# ESC.net
KiCad netlist of a schematic drawn in Altium Designer
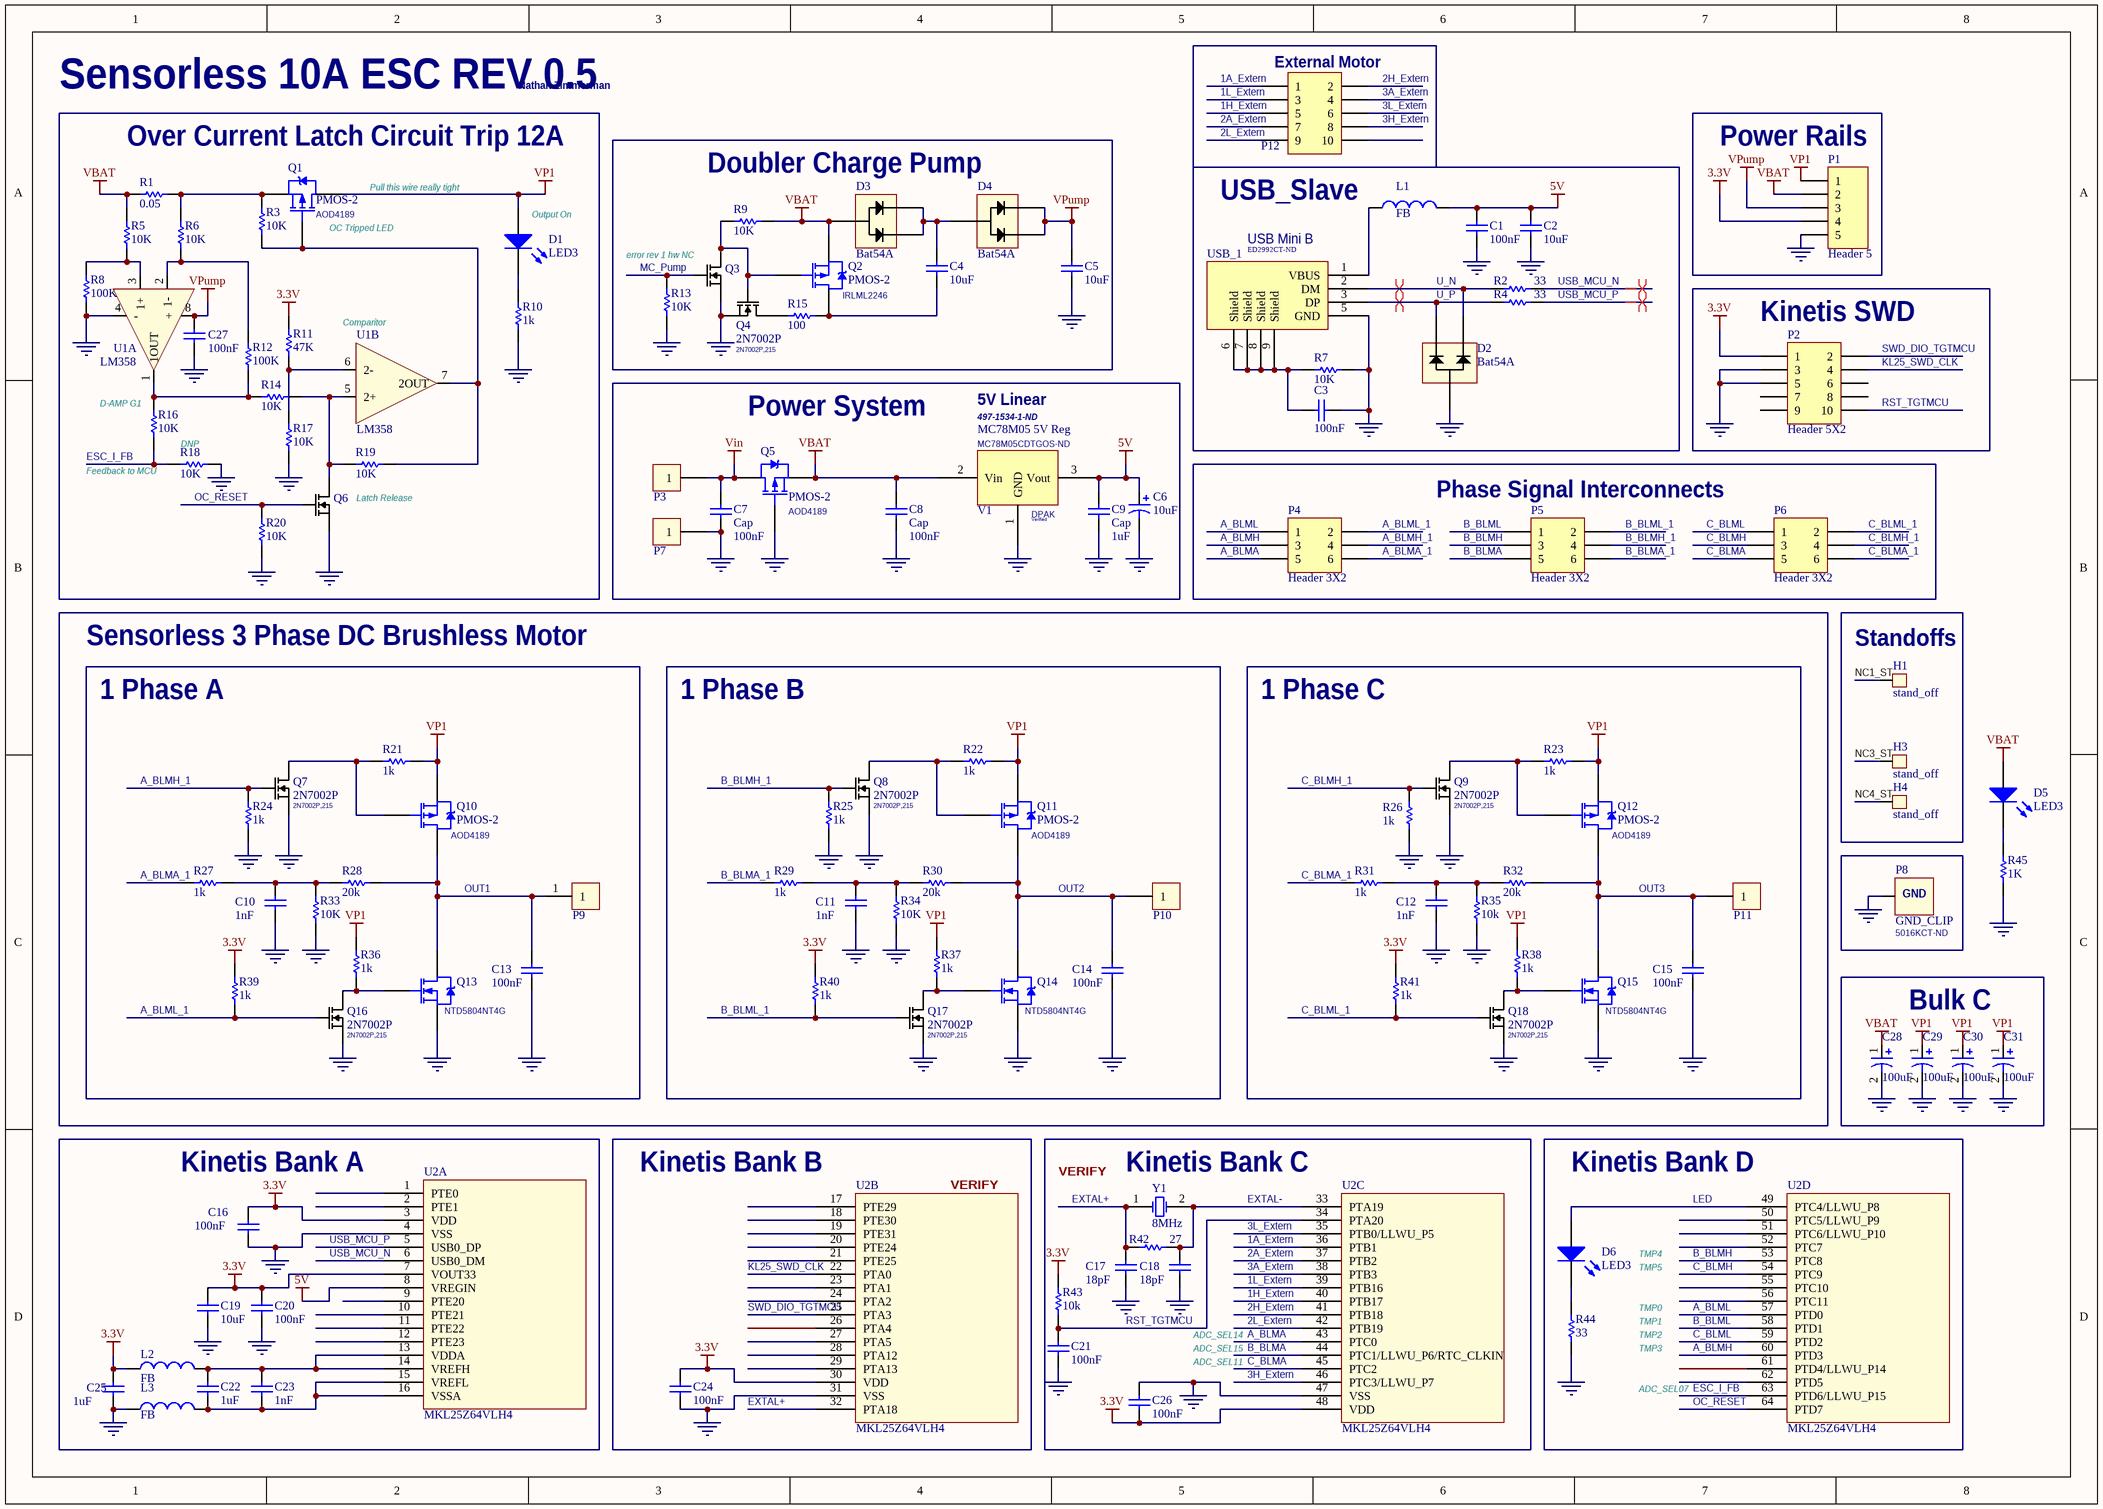
[diagram p0: ESC.SchDoc]

(export (version "E")
  (design (tool "Eeschema 10.0.6"))
  (components
    (comp (ref "C1")
      (value "100nF")
      (footprint "1608[0603]")
      (description "Capacitor (Semiconductor SIM Model)")
      (fields (field (name "Comment") "0805") (field (name "PUBLISHER") "Altium Limited"))
      (libsource (lib "Miscellaneous Devices") (part "Cap Semi"))
    )
    (comp (ref "C2")
      (value "10uF")
      (footprint "C0805")
      (description "Capacitor (Semiconductor SIM Model)")
      (fields (field (name "Comment") "0805") (field (name "PUBLISHER") "Altium Limited"))
      (libsource (lib "Miscellaneous Devices") (part "Cap Semi"))
    )
    (comp (ref "C3")
      (value "100nF")
      (footprint "1608[0603]")
      (description "Capacitor (Semiconductor SIM Model)")
      (fields (field (name "Comment") "0805") (field (name "PUBLISHER") "Altium Limited"))
      (libsource (lib "Miscellaneous Devices") (part "Cap Semi"))
    )
    (comp (ref "C4")
      (value "10uF")
      (footprint "C0805")
      (description "Capacitor (Semiconductor SIM Model)")
      (fields (field (name "Comment") "0805") (field (name "PUBLISHER") "Altium Limited"))
      (libsource (lib "Miscellaneous Devices") (part "Cap Semi"))
    )
    (comp (ref "C5")
      (value "10uF")
      (footprint "C0805")
      (description "Capacitor (Semiconductor SIM Model)")
      (fields (field (name "Comment") "0805") (field (name "PUBLISHER") "Altium Limited"))
      (libsource (lib "Miscellaneous Devices") (part "Cap Semi"))
    )
    (comp (ref "C6")
      (value "10uF")
      (footprint "1206_C")
      (description "Polarized Capacitor (Radial)")
      (fields (field (name "Comment") "Cap Pol1"))
      (libsource (lib "Miscellaneous Devices") (part "Cap Pol1"))
    )
    (comp (ref "C7")
      (value "Cap")
      (footprint "C0805")
      (description "Capacitor")
      (fields (field (name "ALTIUM_VALUE") "100nF") (field (name "PUBLISHER") "Altium Limited"))
      (libsource (lib "Miscellaneous Devices") (part "Cap"))
    )
    (comp (ref "C8")
      (value "Cap")
      (footprint "C0805")
      (description "Capacitor")
      (fields (field (name "ALTIUM_VALUE") "100nF") (field (name "PUBLISHER") "Altium Limited"))
      (libsource (lib "Miscellaneous Devices") (part "Cap"))
    )
    (comp (ref "C9")
      (value "Cap")
      (footprint "C0805")
      (description "Capacitor")
      (fields (field (name "ALTIUM_VALUE") "1uF") (field (name "PUBLISHER") "Altium Limited"))
      (libsource (lib "Miscellaneous Devices") (part "Cap"))
    )
    (comp (ref "C10")
      (value "1nF")
      (footprint "1608[0603]")
      (description "Capacitor (Semiconductor SIM Model)")
      (fields (field (name "Comment") "0805") (field (name "PUBLISHER") "Altium Limited"))
      (libsource (lib "Miscellaneous Devices") (part "Cap Semi"))
    )
    (comp (ref "C11")
      (value "1nF")
      (footprint "1608[0603]")
      (description "Capacitor (Semiconductor SIM Model)")
      (fields (field (name "Comment") "0805") (field (name "PUBLISHER") "Altium Limited"))
      (libsource (lib "Miscellaneous Devices") (part "Cap Semi"))
    )
    (comp (ref "C12")
      (value "1nF")
      (footprint "1608[0603]")
      (description "Capacitor (Semiconductor SIM Model)")
      (fields (field (name "Comment") "0805") (field (name "PUBLISHER") "Altium Limited"))
      (libsource (lib "Miscellaneous Devices") (part "Cap Semi"))
    )
    (comp (ref "C13")
      (value "100nF")
      (footprint "1608[0603]")
      (description "Capacitor (Semiconductor SIM Model)")
      (fields (field (name "Comment") "0805") (field (name "PUBLISHER") "Altium Limited"))
      (libsource (lib "Miscellaneous Devices") (part "Cap Semi"))
    )
    (comp (ref "C14")
      (value "100nF")
      (footprint "1608[0603]")
      (description "Capacitor (Semiconductor SIM Model)")
      (fields (field (name "Comment") "0805") (field (name "PUBLISHER") "Altium Limited"))
      (libsource (lib "Miscellaneous Devices") (part "Cap Semi"))
    )
    (comp (ref "C15")
      (value "100nF")
      (footprint "1608[0603]")
      (description "Capacitor (Semiconductor SIM Model)")
      (fields (field (name "Comment") "0805") (field (name "PUBLISHER") "Altium Limited"))
      (libsource (lib "Miscellaneous Devices") (part "Cap Semi"))
    )
    (comp (ref "C16")
      (value "100nF")
      (footprint "1608[0603]")
      (description "Capacitor (Semiconductor SIM Model)")
      (fields (field (name "Comment") "0805") (field (name "PUBLISHER") "Altium Limited"))
      (libsource (lib "Miscellaneous Devices") (part "Cap Semi"))
    )
    (comp (ref "C17")
      (value "18pF")
      (footprint "1608[0603]")
      (description "Capacitor (Semiconductor SIM Model)")
      (fields (field (name "Comment") "0805") (field (name "PUBLISHER") "Altium Limited"))
      (libsource (lib "Miscellaneous Devices") (part "Cap Semi"))
    )
    (comp (ref "C18")
      (value "18pF")
      (footprint "1608[0603]")
      (description "Capacitor (Semiconductor SIM Model)")
      (fields (field (name "Comment") "0805") (field (name "PUBLISHER") "Altium Limited"))
      (libsource (lib "Miscellaneous Devices") (part "Cap Semi"))
    )
    (comp (ref "C19")
      (value "10uF")
      (footprint "C0805")
      (description "Capacitor (Semiconductor SIM Model)")
      (fields (field (name "Comment") "0805") (field (name "PUBLISHER") "Altium Limited"))
      (libsource (lib "Miscellaneous Devices") (part "Cap Semi"))
    )
    (comp (ref "C20")
      (value "100nF")
      (footprint "1608[0603]")
      (description "Capacitor (Semiconductor SIM Model)")
      (fields (field (name "Comment") "0805") (field (name "PUBLISHER") "Altium Limited"))
      (libsource (lib "Miscellaneous Devices") (part "Cap Semi"))
    )
    (comp (ref "C21")
      (value "100nF")
      (footprint "1608[0603]")
      (description "Capacitor (Semiconductor SIM Model)")
      (fields (field (name "Comment") "0805") (field (name "PUBLISHER") "Altium Limited"))
      (libsource (lib "Miscellaneous Devices") (part "Cap Semi"))
    )
    (comp (ref "C22")
      (value "1uF")
      (footprint "1608[0603]")
      (description "Capacitor (Semiconductor SIM Model)")
      (fields (field (name "Comment") "0805") (field (name "PUBLISHER") "Altium Limited"))
      (libsource (lib "Miscellaneous Devices") (part "Cap Semi"))
    )
    (comp (ref "C23")
      (value "1nF")
      (footprint "1608[0603]")
      (description "Capacitor (Semiconductor SIM Model)")
      (fields (field (name "Comment") "0805") (field (name "PUBLISHER") "Altium Limited"))
      (libsource (lib "Miscellaneous Devices") (part "Cap Semi"))
    )
    (comp (ref "C24")
      (value "100nF")
      (footprint "1608[0603]")
      (description "Capacitor (Semiconductor SIM Model)")
      (fields (field (name "Comment") "0805") (field (name "PUBLISHER") "Altium Limited"))
      (libsource (lib "Miscellaneous Devices") (part "Cap Semi"))
    )
    (comp (ref "C25")
      (value "1uF")
      (footprint "1608[0603]")
      (description "Capacitor (Semiconductor SIM Model)")
      (fields (field (name "Comment") "0805") (field (name "PUBLISHER") "Altium Limited"))
      (libsource (lib "Miscellaneous Devices") (part "Cap Semi"))
    )
    (comp (ref "C26")
      (value "100nF")
      (footprint "1608[0603]")
      (description "Capacitor (Semiconductor SIM Model)")
      (fields (field (name "Comment") "0805") (field (name "PUBLISHER") "Altium Limited"))
      (libsource (lib "Miscellaneous Devices") (part "Cap Semi"))
    )
    (comp (ref "C27")
      (value "100nF")
      (footprint "1608[0603]")
      (description "Capacitor (Semiconductor SIM Model)")
      (fields (field (name "Comment") "0805"))
      (libsource (lib "Miscellaneous Devices") (part "Cap Semi"))
    )
    (comp (ref "C28")
      (value "100uF")
      (footprint "ELE_CAP")
      (description "Polarized Capacitor (Radial)")
      (fields (field (name "Comment") "Cap Pol1"))
      (libsource (lib "") (part "Cap Pol1_1"))
    )
    (comp (ref "C29")
      (value "100uF")
      (footprint "ELE_CAP")
      (description "Polarized Capacitor (Radial)")
      (fields (field (name "Comment") "Cap Pol1"))
      (libsource (lib "") (part "Cap Pol1_1"))
    )
    (comp (ref "C30")
      (value "100uF")
      (footprint "ELE_CAP")
      (description "Polarized Capacitor (Radial)")
      (fields (field (name "Comment") "Cap Pol1"))
      (libsource (lib "") (part "Cap Pol1_1"))
    )
    (comp (ref "C31")
      (value "100uF")
      (footprint "ELE_CAP")
      (description "Polarized Capacitor (Radial)")
      (fields (field (name "Comment") "Cap Pol1"))
      (libsource (lib "") (part "Cap Pol1_1"))
    )
    (comp (ref "D1")
      (value "LED3")
      (footprint "6-0805_L")
      (description "Typical BLUE SiC LED")
      (fields (field (name "PUBLISHER") "Altium Limited"))
      (libsource (lib "Miscellaneous Devices") (part "LED3"))
    )
    (comp (ref "D2")
      (value "Bat54A")
      (footprint "SOT-23B_N")
      (description "Bat45C")
      (libsource (lib "GSOT05CGS08") (part "Bat45C"))
    )
    (comp (ref "D3")
      (value "Bat54A")
      (footprint "SOT-23B_N")
      (description "Bat45C")
      (libsource (lib "GSOT05CGS08") (part "Bat45C"))
    )
    (comp (ref "D4")
      (value "Bat54A")
      (footprint "SOT-23B_N")
      (description "Bat45C")
      (libsource (lib "GSOT05CGS08") (part "Bat45C"))
    )
    (comp (ref "D5")
      (value "LED3")
      (footprint "6-0805_L")
      (description "Typical BLUE SiC LED")
      (fields (field (name "PUBLISHER") "Altium Limited"))
      (libsource (lib "Miscellaneous Devices") (part "LED3"))
    )
    (comp (ref "D6")
      (value "LED3")
      (footprint "6-0805_L")
      (description "Typical BLUE SiC LED")
      (fields (field (name "PUBLISHER") "Altium Limited"))
      (libsource (lib "Miscellaneous Devices") (part "LED3"))
    )
    (comp (ref "H1")
      (value "stand_off")
      (footprint "4-40_screw_hole")
      (libsource (lib "pcb_standoff") (part "stand_off"))
    )
    (comp (ref "H3")
      (value "stand_off")
      (footprint "4-40_screw_hole")
      (libsource (lib "pcb_standoff") (part "stand_off"))
    )
    (comp (ref "H4")
      (value "stand_off")
      (footprint "4-40_screw_hole")
      (libsource (lib "pcb_standoff") (part "stand_off"))
    )
    (comp (ref "L1")
      (value "FB")
      (footprint "1608[0603]")
      (description "Inductor")
      (libsource (lib "Miscellaneous Devices") (part "Inductor"))
    )
    (comp (ref "L2")
      (value "FB")
      (footprint "1608[0603]")
      (description "Inductor")
      (libsource (lib "Miscellaneous Devices") (part "Inductor"))
    )
    (comp (ref "L3")
      (value "FB")
      (footprint "1608[0603]")
      (description "Inductor")
      (libsource (lib "Miscellaneous Devices") (part "Inductor"))
    )
    (comp (ref "P1")
      (value "Header 5")
      (footprint "HDR1X5")
      (description "Header, 5-Pin")
      (fields (field (name "PUBLISHER") "Altium Limited"))
      (libsource (lib "Miscellaneous Connectors") (part "Header 5"))
    )
    (comp (ref "P2")
      (value "Header 5X2")
      (footprint "MHDR2X5")
      (description "Header, 5-Pin, Dual row")
      (fields (field (name "PUBLISHER") "Altium Limited"))
      (libsource (lib "Miscellaneous Connectors") (part "Header 5X2"))
    )
    (comp (ref "P3") (value "Header") (footprint "8191_K") (libsource (lib "Header1") (part "Header1h1")))
    (comp (ref "P4")
      (value "Header 3X2")
      (footprint "HDR2X3")
      (description "Header, 3-Pin, Dual row")
      (fields (field (name "PUBLISHER") "Altium Limited"))
      (libsource (lib "Miscellaneous Connectors") (part "Header 3X2"))
    )
    (comp (ref "P5")
      (value "Header 3X2")
      (footprint "HDR2X3")
      (description "Header, 3-Pin, Dual row")
      (fields (field (name "PUBLISHER") "Altium Limited"))
      (libsource (lib "Miscellaneous Connectors") (part "Header 3X2"))
    )
    (comp (ref "P6")
      (value "Header 3X2")
      (footprint "HDR2X3")
      (description "Header, 3-Pin, Dual row")
      (fields (field (name "PUBLISHER") "Altium Limited"))
      (libsource (lib "Miscellaneous Connectors") (part "Header 3X2"))
    )
    (comp (ref "P7") (value "Header") (footprint "8191_K") (libsource (lib "Header1") (part "Header1h1")))
    (comp (ref "P8")
      (value "GND_CLIP")
      (footprint "GND_CLIP")
      (fields (field (name "ALTIUM_UNNAMED_1") "5016KCT-ND"))
      (libsource (lib "GND_CLIP") (part "GND_CLIP"))
    )
    (comp (ref "P9") (value "Header") (footprint "8191_K") (libsource (lib "") (part "Header1h1_1")))
    (comp (ref "P10") (value "Header") (footprint "8191_K") (libsource (lib "Header1") (part "Header1h1")))
    (comp (ref "P11") (value "Header") (footprint "8191_K") (libsource (lib "Header1") (part "Header1h1")))
    (comp (ref "P12")
      (value "Header 5X2")
      (footprint "HDR2X5")
      (description "Header, 5-Pin, Dual row")
      (fields (field (name "PUBLISHER") "Altium Limited"))
      (libsource (lib "Miscellaneous Connectors") (part "Header 5X2"))
    )
    (comp (ref "Q1")
      (value "PMOS-2")
      (footprint "TO228P970-3_4AM")
      (description "P-Channel Power MOSFET")
      (fields (field (name "ALTIUM_UNNAMED_1") "AOD4189"))
      (libsource (lib "Miscellaneous Devices") (part "PMOS-2"))
    )
    (comp (ref "Q2")
      (value "PMOS-2")
      (footprint "SOT-23_M")
      (description "P-Channel Power MOSFET")
      (fields (field (name "ALTIUM_UNNAMED_1") "IRLML2246"))
      (libsource (lib "") (part "PMOS-2_1"))
    )
    (comp (ref "Q3") (value "2N7002P") (footprint "SOT-23_M") (libsource (lib "2N7002P215") (part "2N7002P")))
    (comp (ref "Q4")
      (value "2N7002P")
      (footprint "SOT-23_M")
      (fields (field (name "ALTIUM_UNNAMED_1") "2N7002P,215"))
      (libsource (lib "2N7002P215") (part "2N7002P"))
    )
    (comp (ref "Q5")
      (value "PMOS-2")
      (footprint "TO228P970-3_4AM")
      (description "P-Channel Power MOSFET")
      (fields (field (name "ALTIUM_UNNAMED_1") "AOD4189"))
      (libsource (lib "Miscellaneous Devices") (part "PMOS-2"))
    )
    (comp (ref "Q6") (value "2N7002P") (footprint "SOT-23_M") (libsource (lib "2N7002P215") (part "2N7002P")))
    (comp (ref "Q7")
      (value "2N7002P")
      (footprint "SOT-23_M")
      (fields (field (name "ALTIUM_UNNAMED_1") "2N7002P,215"))
      (libsource (lib "2N7002P215") (part "2N7002P"))
    )
    (comp (ref "Q8")
      (value "2N7002P")
      (footprint "SOT-23_M")
      (fields (field (name "ALTIUM_UNNAMED_1") "2N7002P,215"))
      (libsource (lib "2N7002P215") (part "2N7002P"))
    )
    (comp (ref "Q9")
      (value "2N7002P")
      (footprint "SOT-23_M")
      (fields (field (name "ALTIUM_UNNAMED_1") "2N7002P,215"))
      (libsource (lib "2N7002P215") (part "2N7002P"))
    )
    (comp (ref "Q10")
      (value "PMOS-2")
      (footprint "TO228P970-3_4AM")
      (description "P-Channel Power MOSFET")
      (fields (field (name "ALTIUM_UNNAMED_1") "AOD4189"))
      (libsource (lib "Miscellaneous Devices") (part "PMOS-2"))
    )
    (comp (ref "Q11")
      (value "PMOS-2")
      (footprint "TO228P970-3_4AM")
      (description "P-Channel Power MOSFET")
      (fields (field (name "ALTIUM_UNNAMED_1") "AOD4189"))
      (libsource (lib "Miscellaneous Devices") (part "PMOS-2"))
    )
    (comp (ref "Q12")
      (value "PMOS-2")
      (footprint "TO228P970-3_4AM")
      (description "P-Channel Power MOSFET")
      (fields (field (name "ALTIUM_UNNAMED_1") "AOD4189"))
      (libsource (lib "Miscellaneous Devices") (part "PMOS-2"))
    )
    (comp (ref "Q13")
      (value "NMOS-2")
      (footprint "TO228P970-3_4AM")
      (description "N-Channel Power MOSFET")
      (fields (field (name "ALTIUM_UNNAMED_1") "NTD5804NT4G"))
      (libsource (lib "Miscellaneous Devices") (part "NMOS-2"))
    )
    (comp (ref "Q14")
      (value "NMOS-2")
      (footprint "TO228P970-3_4AM")
      (description "N-Channel Power MOSFET")
      (fields (field (name "ALTIUM_UNNAMED_1") "NTD5804NT4G"))
      (libsource (lib "Miscellaneous Devices") (part "NMOS-2"))
    )
    (comp (ref "Q15")
      (value "NMOS-2")
      (footprint "TO228P970-3_4AM")
      (description "N-Channel Power MOSFET")
      (fields (field (name "ALTIUM_UNNAMED_1") "NTD5804NT4G"))
      (libsource (lib "Miscellaneous Devices") (part "NMOS-2"))
    )
    (comp (ref "Q16")
      (value "2N7002P")
      (footprint "SOT-23_M")
      (fields (field (name "ALTIUM_UNNAMED_1") "2N7002P,215"))
      (libsource (lib "2N7002P215") (part "2N7002P"))
    )
    (comp (ref "Q17")
      (value "2N7002P")
      (footprint "SOT-23_M")
      (fields (field (name "ALTIUM_UNNAMED_1") "2N7002P,215"))
      (libsource (lib "2N7002P215") (part "2N7002P"))
    )
    (comp (ref "Q18")
      (value "2N7002P")
      (footprint "SOT-23_M")
      (fields (field (name "ALTIUM_UNNAMED_1") "2N7002P,215"))
      (libsource (lib "2N7002P215") (part "2N7002P"))
    )
    (comp (ref "R1")
      (value "0.05")
      (footprint "RESC6432AM")
      (description "Resistor")
      (fields (field (name "Comment") "Res1") (field (name "PUBLISHER") "Altium Limited"))
      (libsource (lib "Miscellaneous Devices") (part "Res1"))
    )
    (comp (ref "R2")
      (value "33")
      (footprint "1608[0603]")
      (description "Resistor")
      (fields (field (name "Comment") "Res1") (field (name "PUBLISHER") "Altium Limited"))
      (libsource (lib "Miscellaneous Devices") (part "Res1"))
    )
    (comp (ref "R3")
      (value "10K")
      (footprint "1608[0603]")
      (description "Resistor")
      (fields (field (name "Comment") "Res1") (field (name "PUBLISHER") "Altium Limited"))
      (libsource (lib "Miscellaneous Devices") (part "Res1"))
    )
    (comp (ref "R4")
      (value "33")
      (footprint "1608[0603]")
      (description "Resistor")
      (fields (field (name "Comment") "Res1") (field (name "PUBLISHER") "Altium Limited"))
      (libsource (lib "Miscellaneous Devices") (part "Res1"))
    )
    (comp (ref "R5")
      (value "10K")
      (footprint "1608[0603]")
      (description "Resistor")
      (fields (field (name "Comment") "Res1") (field (name "PUBLISHER") "Altium Limited"))
      (libsource (lib "Miscellaneous Devices") (part "Res1"))
    )
    (comp (ref "R6")
      (value "10K")
      (footprint "1608[0603]")
      (description "Resistor")
      (fields (field (name "Comment") "Res1") (field (name "PUBLISHER") "Altium Limited"))
      (libsource (lib "Miscellaneous Devices") (part "Res1"))
    )
    (comp (ref "R7")
      (value "10K")
      (footprint "1608[0603]")
      (description "Resistor")
      (fields (field (name "Comment") "Res1") (field (name "PUBLISHER") "Altium Limited"))
      (libsource (lib "Miscellaneous Devices") (part "Res1"))
    )
    (comp (ref "R8")
      (value "100K")
      (footprint "1608[0603]")
      (description "Resistor")
      (fields (field (name "Comment") "Res1") (field (name "PUBLISHER") "Altium Limited"))
      (libsource (lib "Miscellaneous Devices") (part "Res1"))
    )
    (comp (ref "R9")
      (value "10K")
      (footprint "1608[0603]")
      (description "Resistor")
      (fields (field (name "Comment") "Res1") (field (name "PUBLISHER") "Altium Limited"))
      (libsource (lib "Miscellaneous Devices") (part "Res1"))
    )
    (comp (ref "R10")
      (value "1k")
      (footprint "1608[0603]")
      (description "Resistor")
      (fields (field (name "Comment") "Res1") (field (name "PUBLISHER") "Altium Limited"))
      (libsource (lib "Miscellaneous Devices") (part "Res1"))
    )
    (comp (ref "R11")
      (value "47K")
      (footprint "1608[0603]")
      (description "Resistor")
      (fields (field (name "Comment") "Res1") (field (name "PUBLISHER") "Altium Limited"))
      (libsource (lib "Miscellaneous Devices") (part "Res1"))
    )
    (comp (ref "R12")
      (value "100K")
      (footprint "1608[0603]")
      (description "Resistor")
      (fields (field (name "Comment") "Res1") (field (name "PUBLISHER") "Altium Limited"))
      (libsource (lib "Miscellaneous Devices") (part "Res1"))
    )
    (comp (ref "R13")
      (value "10K")
      (footprint "1608[0603]")
      (description "Resistor")
      (fields (field (name "Comment") "Res1") (field (name "PUBLISHER") "Altium Limited"))
      (libsource (lib "Miscellaneous Devices") (part "Res1"))
    )
    (comp (ref "R14")
      (value "10K")
      (footprint "1608[0603]")
      (description "Resistor")
      (fields (field (name "Comment") "Res1") (field (name "PUBLISHER") "Altium Limited"))
      (libsource (lib "Miscellaneous Devices") (part "Res1"))
    )
    (comp (ref "R15")
      (value "100")
      (footprint "1608[0603]")
      (description "Resistor")
      (fields (field (name "Comment") "Res1") (field (name "PUBLISHER") "Altium Limited"))
      (libsource (lib "Miscellaneous Devices") (part "Res1"))
    )
    (comp (ref "R16")
      (value "10K")
      (footprint "1608[0603]")
      (description "Resistor")
      (fields (field (name "Comment") "Res1") (field (name "PUBLISHER") "Altium Limited"))
      (libsource (lib "Miscellaneous Devices") (part "Res1"))
    )
    (comp (ref "R17")
      (value "10K")
      (footprint "1608[0603]")
      (description "Resistor")
      (fields (field (name "Comment") "Res1") (field (name "PUBLISHER") "Altium Limited"))
      (libsource (lib "Miscellaneous Devices") (part "Res1"))
    )
    (comp (ref "R18")
      (value "10K")
      (footprint "1608[0603]")
      (description "Resistor")
      (fields (field (name "Comment") "Res1") (field (name "PUBLISHER") "Altium Limited"))
      (libsource (lib "Miscellaneous Devices") (part "Res1"))
    )
    (comp (ref "R19")
      (value "10K")
      (footprint "1608[0603]")
      (description "Resistor")
      (fields (field (name "Comment") "Res1") (field (name "PUBLISHER") "Altium Limited"))
      (libsource (lib "Miscellaneous Devices") (part "Res1"))
    )
    (comp (ref "R20")
      (value "10K")
      (footprint "1608[0603]")
      (description "Resistor")
      (fields (field (name "Comment") "Res1") (field (name "PUBLISHER") "Altium Limited"))
      (libsource (lib "Miscellaneous Devices") (part "Res1"))
    )
    (comp (ref "R21")
      (value "1k")
      (footprint "1608[0603]")
      (description "Resistor")
      (fields (field (name "Comment") "Res1") (field (name "PUBLISHER") "Altium Limited"))
      (libsource (lib "Miscellaneous Devices") (part "Res1"))
    )
    (comp (ref "R22")
      (value "1k")
      (footprint "1608[0603]")
      (description "Resistor")
      (fields (field (name "Comment") "Res1") (field (name "PUBLISHER") "Altium Limited"))
      (libsource (lib "Miscellaneous Devices") (part "Res1"))
    )
    (comp (ref "R23")
      (value "1k")
      (footprint "1608[0603]")
      (description "Resistor")
      (fields (field (name "Comment") "Res1") (field (name "PUBLISHER") "Altium Limited"))
      (libsource (lib "Miscellaneous Devices") (part "Res1"))
    )
    (comp (ref "R24")
      (value "1k")
      (footprint "1608[0603]")
      (description "Resistor")
      (fields (field (name "Comment") "Res1") (field (name "PUBLISHER") "Altium Limited"))
      (libsource (lib "Miscellaneous Devices") (part "Res1"))
    )
    (comp (ref "R25")
      (value "1k")
      (footprint "1608[0603]")
      (description "Resistor")
      (fields (field (name "Comment") "Res1") (field (name "PUBLISHER") "Altium Limited"))
      (libsource (lib "Miscellaneous Devices") (part "Res1"))
    )
    (comp (ref "R26")
      (value "1k")
      (footprint "1608[0603]")
      (description "Resistor")
      (fields (field (name "Comment") "Res1") (field (name "PUBLISHER") "Altium Limited"))
      (libsource (lib "Miscellaneous Devices") (part "Res1"))
    )
    (comp (ref "R27")
      (value "1k")
      (footprint "1608[0603]")
      (description "Resistor")
      (fields (field (name "Comment") "Res1") (field (name "PUBLISHER") "Altium Limited"))
      (libsource (lib "Miscellaneous Devices") (part "Res1"))
    )
    (comp (ref "R28")
      (value "20k")
      (footprint "1608[0603]")
      (description "Resistor")
      (fields (field (name "Comment") "Res1") (field (name "PUBLISHER") "Altium Limited"))
      (libsource (lib "Miscellaneous Devices") (part "Res1"))
    )
    (comp (ref "R29")
      (value "1k")
      (footprint "1608[0603]")
      (description "Resistor")
      (fields (field (name "Comment") "Res1") (field (name "PUBLISHER") "Altium Limited"))
      (libsource (lib "Miscellaneous Devices") (part "Res1"))
    )
    (comp (ref "R30")
      (value "20k")
      (footprint "1608[0603]")
      (description "Resistor")
      (fields (field (name "Comment") "Res1") (field (name "PUBLISHER") "Altium Limited"))
      (libsource (lib "Miscellaneous Devices") (part "Res1"))
    )
    (comp (ref "R31")
      (value "1k")
      (footprint "1608[0603]")
      (description "Resistor")
      (fields (field (name "Comment") "Res1") (field (name "PUBLISHER") "Altium Limited"))
      (libsource (lib "Miscellaneous Devices") (part "Res1"))
    )
    (comp (ref "R32")
      (value "20k")
      (footprint "1608[0603]")
      (description "Resistor")
      (fields (field (name "Comment") "Res1") (field (name "PUBLISHER") "Altium Limited"))
      (libsource (lib "Miscellaneous Devices") (part "Res1"))
    )
    (comp (ref "R33")
      (value "10K")
      (footprint "1608[0603]")
      (description "Resistor")
      (fields (field (name "Comment") "Res1") (field (name "PUBLISHER") "Altium Limited"))
      (libsource (lib "Miscellaneous Devices") (part "Res1"))
    )
    (comp (ref "R34")
      (value "10K")
      (footprint "1608[0603]")
      (description "Resistor")
      (fields (field (name "Comment") "Res1") (field (name "PUBLISHER") "Altium Limited"))
      (libsource (lib "Miscellaneous Devices") (part "Res1"))
    )
    (comp (ref "R35")
      (value "10k")
      (footprint "1608[0603]")
      (description "Resistor")
      (fields (field (name "Comment") "Res1") (field (name "PUBLISHER") "Altium Limited"))
      (libsource (lib "Miscellaneous Devices") (part "Res1"))
    )
    (comp (ref "R36")
      (value "1k")
      (footprint "1608[0603]")
      (description "Resistor")
      (fields (field (name "Comment") "Res1") (field (name "PUBLISHER") "Altium Limited"))
      (libsource (lib "Miscellaneous Devices") (part "Res1"))
    )
    (comp (ref "R37")
      (value "1k")
      (footprint "1608[0603]")
      (description "Resistor")
      (fields (field (name "Comment") "Res1") (field (name "PUBLISHER") "Altium Limited"))
      (libsource (lib "Miscellaneous Devices") (part "Res1"))
    )
    (comp (ref "R38")
      (value "1k")
      (footprint "1608[0603]")
      (description "Resistor")
      (fields (field (name "Comment") "Res1") (field (name "PUBLISHER") "Altium Limited"))
      (libsource (lib "Miscellaneous Devices") (part "Res1"))
    )
    (comp (ref "R39")
      (value "1k")
      (footprint "1608[0603]")
      (description "Resistor")
      (fields (field (name "Comment") "Res1") (field (name "PUBLISHER") "Altium Limited"))
      (libsource (lib "Miscellaneous Devices") (part "Res1"))
    )
    (comp (ref "R40")
      (value "1k")
      (footprint "1608[0603]")
      (description "Resistor")
      (fields (field (name "Comment") "Res1") (field (name "PUBLISHER") "Altium Limited"))
      (libsource (lib "Miscellaneous Devices") (part "Res1"))
    )
    (comp (ref "R41")
      (value "1k")
      (footprint "1608[0603]")
      (description "Resistor")
      (fields (field (name "Comment") "Res1") (field (name "PUBLISHER") "Altium Limited"))
      (libsource (lib "Miscellaneous Devices") (part "Res1"))
    )
    (comp (ref "R42")
      (value "27")
      (footprint "1608[0603]")
      (description "Resistor")
      (fields (field (name "Comment") "Res1") (field (name "PUBLISHER") "Altium Limited"))
      (libsource (lib "Miscellaneous Devices") (part "Res1"))
    )
    (comp (ref "R43")
      (value "10k")
      (footprint "1608[0603]")
      (description "Resistor")
      (fields (field (name "Comment") "Res1") (field (name "PUBLISHER") "Altium Limited"))
      (libsource (lib "Miscellaneous Devices") (part "Res1"))
    )
    (comp (ref "R44")
      (value "33")
      (footprint "1608[0603]")
      (description "Resistor")
      (fields (field (name "Comment") "Res1") (field (name "PUBLISHER") "Altium Limited"))
      (libsource (lib "Miscellaneous Devices") (part "Res1"))
    )
    (comp (ref "R45")
      (value "1K")
      (footprint "1608[0603]")
      (description "Resistor")
      (fields (field (name "Comment") "Res1") (field (name "PUBLISHER") "Altium Limited"))
      (libsource (lib "Miscellaneous Devices") (part "Res1"))
    )
    (comp (ref "U1")
      (value "LM358")
      (footprint "SOIC127P600-8BM")
      (description "LM358 Op Amp")
      (libsource (lib "LM358_New") (part "LM358"))
    )
    (comp (ref "U2")
      (value "MKL25Z64VLH4")
      (footprint "TSQFP50P1200X1200-64M")
      (description "MKL25Z64VLH4 MCU")
      (libsource (lib "MKL25Z64VLH4") (part "MKL25Z64VLH4"))
    )
    (comp (ref "USB_1")
      (value "USB-M2xFxx")
      (footprint "USB-M2xFxx")
      (description "USB Mini-B for USB-M2xFxx")
      (fields (field (name "DIGIKEY") "ED2992CT-ND"))
      (libsource (lib "USB-M2xFxx") (part "USB-M2xFxx"))
    )
    (comp (ref "V1")
      (value "MC78M05 5V Reg")
      (footprint "TO228P970-3_4AM")
      (description "MCP1702 5V REG")
      (fields (field (name "ALTIUM_UNNAMED_1") "497-1534-1-ND"))
      (libsource (lib "MCP1702") (part "MCP1702"))
    )
    (comp (ref "Y1")
      (value "8MHz")
      (footprint "crystal")
      (description "Crystal Oscillator")
      (libsource (lib "Miscellaneous Devices") (part "XTAL"))
    )
  )
  (nets
    (net (code "1") (name "/1A_Extern") (class "Default")
      (node (ref "P12") (pin "1") (pinfunction "1_1") (pintype "passive"))
      (node (ref "U2") (pin "36") (pinfunction "PTB1_36") (pintype "passive"))
    )
    (net (code "2") (name "/1H_Extern") (class "Default")
      (node (ref "P12") (pin "5") (pinfunction "5_5") (pintype "passive"))
      (node (ref "U2") (pin "40") (pinfunction "PTB17_40") (pintype "passive"))
    )
    (net (code "3") (name "/1L_Extern") (class "Default")
      (node (ref "P12") (pin "3") (pinfunction "3_3") (pintype "passive"))
      (node (ref "U2") (pin "39") (pinfunction "PTB16_39") (pintype "passive"))
    )
    (net (code "4") (name "/2A_Extern") (class "Default")
      (node (ref "P12") (pin "7") (pinfunction "7_7") (pintype "passive"))
      (node (ref "U2") (pin "37") (pinfunction "PTB2_37") (pintype "passive"))
    )
    (net (code "5") (name "/2H_Extern") (class "Default")
      (node (ref "P12") (pin "2") (pinfunction "2_2") (pintype "passive"))
      (node (ref "U2") (pin "41") (pinfunction "PTB18_41") (pintype "passive"))
    )
    (net (code "6") (name "/2L_Extern") (class "Default")
      (node (ref "P12") (pin "9") (pinfunction "9_9") (pintype "passive"))
      (node (ref "U2") (pin "42") (pinfunction "PTB19_42") (pintype "passive"))
    )
    (net (code "7") (name "/3A_Extern") (class "Default")
      (node (ref "P12") (pin "4") (pinfunction "4_4") (pintype "passive"))
      (node (ref "U2") (pin "38") (pinfunction "PTB3_38") (pintype "passive"))
    )
    (net (code "8") (name "/3H_Extern") (class "Default")
      (node (ref "P12") (pin "8") (pinfunction "8_8") (pintype "passive"))
      (node (ref "U2") (pin "46") (pinfunction "PTC3/LLWU_P7_46") (pintype "passive"))
    )
    (net (code "9") (name "/3L_Extern") (class "Default")
      (node (ref "P12") (pin "6") (pinfunction "6_6") (pintype "passive"))
      (node (ref "U2") (pin "35") (pinfunction "PTB0/LLWU_P5_35") (pintype "passive"))
    )
    (net (code "10") (name "/A_BLMA") (class "Default")
      (node (ref "P4") (pin "5") (pinfunction "5_5") (pintype "passive"))
      (node (ref "U2") (pin "43") (pinfunction "PTC0_43") (pintype "passive"))
    )
    (net (code "11") (name "/A_BLMA_1") (class "Default")
      (node (ref "P4") (pin "6") (pinfunction "6_6") (pintype "passive"))
      (node (ref "R27") (pin "2") (pinfunction "2_2") (pintype "passive"))
    )
    (net (code "12") (name "/A_BLMH") (class "Default")
      (node (ref "P4") (pin "3") (pinfunction "3_3") (pintype "passive"))
      (node (ref "U2") (pin "60") (pinfunction "PTD3_60") (pintype "passive"))
    )
    (net (code "13") (name "/A_BLMH_1") (class "Default")
      (node (ref "P4") (pin "4") (pinfunction "4_4") (pintype "passive"))
      (node (ref "Q7") (pin "1") (pinfunction "G_1") (pintype "passive"))
      (node (ref "R24") (pin "1") (pinfunction "1_1") (pintype "passive"))
    )
    (net (code "14") (name "/A_BLML") (class "Default")
      (node (ref "P4") (pin "1") (pinfunction "1_1") (pintype "passive"))
      (node (ref "U2") (pin "57") (pinfunction "PTD0_57") (pintype "passive"))
    )
    (net (code "15") (name "/A_BLML_1") (class "Default")
      (node (ref "P4") (pin "2") (pinfunction "2_2") (pintype "passive"))
      (node (ref "Q16") (pin "1") (pinfunction "G_1") (pintype "passive"))
      (node (ref "R39") (pin "2") (pinfunction "2_2") (pintype "passive"))
    )
    (net (code "16") (name "/B_BLMA") (class "Default")
      (node (ref "P5") (pin "5") (pinfunction "5_5") (pintype "passive"))
      (node (ref "U2") (pin "44") (pinfunction "PTC1/LLWU_P6/RTC_CLKIN_44") (pintype "passive"))
    )
    (net (code "17") (name "/B_BLMA_1") (class "Default")
      (node (ref "P5") (pin "6") (pinfunction "6_6") (pintype "passive"))
      (node (ref "R29") (pin "2") (pinfunction "2_2") (pintype "passive"))
    )
    (net (code "18") (name "/B_BLMH") (class "Default")
      (node (ref "P5") (pin "3") (pinfunction "3_3") (pintype "passive"))
      (node (ref "U2") (pin "53") (pinfunction "PTC8_53") (pintype "passive"))
    )
    (net (code "19") (name "/B_BLMH_1") (class "Default")
      (node (ref "P5") (pin "4") (pinfunction "4_4") (pintype "passive"))
      (node (ref "Q8") (pin "1") (pinfunction "G_1") (pintype "passive"))
      (node (ref "R25") (pin "1") (pinfunction "1_1") (pintype "passive"))
    )
    (net (code "20") (name "/B_BLML") (class "Default")
      (node (ref "P5") (pin "1") (pinfunction "1_1") (pintype "passive"))
      (node (ref "U2") (pin "58") (pinfunction "PTD1_58") (pintype "passive"))
    )
    (net (code "21") (name "/B_BLML_1") (class "Default")
      (node (ref "P5") (pin "2") (pinfunction "2_2") (pintype "passive"))
      (node (ref "Q17") (pin "1") (pinfunction "G_1") (pintype "passive"))
      (node (ref "R40") (pin "2") (pinfunction "2_2") (pintype "passive"))
    )
    (net (code "22") (name "/C_BLMA") (class "Default")
      (node (ref "P6") (pin "5") (pinfunction "5_5") (pintype "passive"))
      (node (ref "U2") (pin "45") (pinfunction "PTC2_45") (pintype "passive"))
    )
    (net (code "23") (name "/C_BLMA_1") (class "Default")
      (node (ref "P6") (pin "6") (pinfunction "6_6") (pintype "passive"))
      (node (ref "R31") (pin "2") (pinfunction "2_2") (pintype "passive"))
    )
    (net (code "24") (name "/C_BLMH") (class "Default")
      (node (ref "P6") (pin "3") (pinfunction "3_3") (pintype "passive"))
      (node (ref "U2") (pin "54") (pinfunction "PTC9_54") (pintype "passive"))
    )
    (net (code "25") (name "/C_BLMH_1") (class "Default")
      (node (ref "P6") (pin "4") (pinfunction "4_4") (pintype "passive"))
      (node (ref "Q9") (pin "1") (pinfunction "G_1") (pintype "passive"))
      (node (ref "R26") (pin "1") (pinfunction "1_1") (pintype "passive"))
    )
    (net (code "26") (name "/C_BLML") (class "Default")
      (node (ref "P6") (pin "1") (pinfunction "1_1") (pintype "passive"))
      (node (ref "U2") (pin "59") (pinfunction "PTD2_59") (pintype "passive"))
    )
    (net (code "27") (name "/C_BLML_1") (class "Default")
      (node (ref "P6") (pin "2") (pinfunction "2_2") (pintype "passive"))
      (node (ref "Q18") (pin "1") (pinfunction "G_1") (pintype "passive"))
      (node (ref "R41") (pin "2") (pinfunction "2_2") (pintype "passive"))
    )
    (net (code "28") (name "/ESC_I_FB") (class "Default")
      (node (ref "R16") (pin "1") (pinfunction "1_1") (pintype "passive"))
      (node (ref "R18") (pin "2") (pinfunction "2_2") (pintype "passive"))
      (node (ref "U2") (pin "63") (pinfunction "PTD6/LLWU_P15_63") (pintype "passive"))
    )
    (net (code "29") (name "/EXTAL+") (class "Default")
      (node (ref "C17") (pin "2") (pinfunction "2_2") (pintype "passive"))
      (node (ref "R42") (pin "1") (pinfunction "1_1") (pintype "passive"))
      (node (ref "U2") (pin "32") (pinfunction "PTA18_32") (pintype "passive"))
      (node (ref "Y1") (pin "1") (pinfunction "OSC1_1") (pintype "passive"))
    )
    (net (code "30") (name "/EXTAL-") (class "Default")
      (node (ref "C18") (pin "2") (pinfunction "2_2") (pintype "passive"))
      (node (ref "R42") (pin "2") (pinfunction "2_2") (pintype "passive"))
      (node (ref "U2") (pin "33") (pinfunction "PTA19_33") (pintype "passive"))
      (node (ref "Y1") (pin "2") (pinfunction "OSC2_2") (pintype "passive"))
    )
    (net (code "31") (name "/KL25_SWD_CLK") (class "Default")
      (node (ref "P2") (pin "4") (pinfunction "4_4") (pintype "passive"))
      (node (ref "U2") (pin "22") (pinfunction "PTA0_22") (pintype "passive"))
    )
    (net (code "32") (name "/LED") (class "Default")
      (node (ref "D6") (pin "1") (pinfunction "A_1") (pintype "passive"))
      (node (ref "U2") (pin "49") (pinfunction "PTC4/LLWU_P8_49") (pintype "passive"))
    )
    (net (code "33") (name "/MC_Pump") (class "Default")
      (node (ref "Q3") (pin "1") (pinfunction "G_1") (pintype "passive"))
      (node (ref "R13") (pin "1") (pinfunction "1_1") (pintype "passive"))
    )
    (net (code "34") (name "/NC1_ST") (class "Default")
      (node (ref "H1") (pin "1") (pinfunction "0_1") (pintype "passive"))
    )
    (net (code "35") (name "/NC3_ST") (class "Default")
      (node (ref "H3") (pin "1") (pinfunction "0_1") (pintype "passive"))
    )
    (net (code "36") (name "/NC4_ST") (class "Default")
      (node (ref "H4") (pin "1") (pinfunction "0_1") (pintype "passive"))
    )
    (net (code "37") (name "/OC_RESET") (class "Default")
      (node (ref "Q6") (pin "1") (pinfunction "G_1") (pintype "passive"))
      (node (ref "R20") (pin "1") (pinfunction "1_1") (pintype "passive"))
      (node (ref "U2") (pin "64") (pinfunction "PTD7_64") (pintype "passive"))
    )
    (net (code "38") (name "/OUT1") (class "Default")
      (node (ref "C13") (pin "2") (pinfunction "2_2") (pintype "passive"))
      (node (ref "P9") (pin "1") (pinfunction "1_1") (pintype "passive"))
      (node (ref "Q10") (pin "4") (pinfunction "D_4") (pintype "passive"))
      (node (ref "Q13") (pin "4") (pinfunction "D_4") (pintype "passive"))
      (node (ref "R28") (pin "1") (pinfunction "1_1") (pintype "passive"))
    )
    (net (code "39") (name "/OUT2") (class "Default")
      (node (ref "C14") (pin "2") (pinfunction "2_2") (pintype "passive"))
      (node (ref "P10") (pin "1") (pinfunction "1_1") (pintype "passive"))
      (node (ref "Q11") (pin "4") (pinfunction "D_4") (pintype "passive"))
      (node (ref "Q14") (pin "4") (pinfunction "D_4") (pintype "passive"))
      (node (ref "R30") (pin "1") (pinfunction "1_1") (pintype "passive"))
    )
    (net (code "40") (name "/OUT3") (class "Default")
      (node (ref "C15") (pin "2") (pinfunction "2_2") (pintype "passive"))
      (node (ref "P11") (pin "1") (pinfunction "1_1") (pintype "passive"))
      (node (ref "Q12") (pin "4") (pinfunction "D_4") (pintype "passive"))
      (node (ref "Q15") (pin "4") (pinfunction "D_4") (pintype "passive"))
      (node (ref "R32") (pin "1") (pinfunction "1_1") (pintype "passive"))
    )
    (net (code "41") (name "/RST_TGTMCU") (class "Default")
      (node (ref "C21") (pin "2") (pinfunction "2_2") (pintype "passive"))
      (node (ref "P2") (pin "10") (pinfunction "10_10") (pintype "passive"))
      (node (ref "R43") (pin "1") (pinfunction "1_1") (pintype "passive"))
      (node (ref "U2") (pin "34") (pinfunction "PTA20_34") (pintype "passive"))
    )
    (net (code "42") (name "/SWD_DIO_TGTMCU") (class "Default")
      (node (ref "P2") (pin "2") (pinfunction "2_2") (pintype "passive"))
      (node (ref "U2") (pin "25") (pinfunction "PTA3_25") (pintype "passive"))
    )
    (net (code "43") (name "/USB_MCU_N") (class "Default")
      (node (ref "R2") (pin "2") (pinfunction "2_2") (pintype "passive"))
      (node (ref "U2") (pin "6") (pinfunction "USB0_DM_6") (pintype "passive"))
    )
    (net (code "44") (name "/USB_MCU_P") (class "Default")
      (node (ref "R4") (pin "2") (pinfunction "2_2") (pintype "passive"))
      (node (ref "U2") (pin "5") (pinfunction "USB0_DP_5") (pintype "passive"))
    )
    (net (code "45") (name "/U_N") (class "Default")
      (node (ref "D2") (pin "1") (pinfunction "0_1") (pintype "passive"))
      (node (ref "R2") (pin "1") (pinfunction "1_1") (pintype "passive"))
      (node (ref "USB_1") (pin "2") (pinfunction "DM_2") (pintype "passive"))
    )
    (net (code "46") (name "/U_P") (class "Default")
      (node (ref "D2") (pin "2") (pinfunction "0_2") (pintype "passive"))
      (node (ref "R4") (pin "1") (pinfunction "1_1") (pintype "passive"))
      (node (ref "USB_1") (pin "3") (pinfunction "DP_3") (pintype "passive"))
    )
    (net (code "47") (name "3.3V") (class "Default")
      (node (ref "C16") (pin "2") (pinfunction "2_2") (pintype "passive"))
      (node (ref "C19") (pin "1") (pinfunction "1_1") (pintype "passive"))
      (node (ref "C20") (pin "1") (pinfunction "1_1") (pintype "passive"))
      (node (ref "C24") (pin "2") (pinfunction "2_2") (pintype "passive"))
      (node (ref "C25") (pin "2") (pinfunction "2_2") (pintype "passive"))
      (node (ref "C26") (pin "1") (pinfunction "1_1") (pintype "passive"))
      (node (ref "L2") (pin "2") (pinfunction "2_2") (pintype "passive"))
      (node (ref "P1") (pin "4") (pinfunction "4_4") (pintype "passive"))
      (node (ref "P2") (pin "1") (pinfunction "1_1") (pintype "passive"))
      (node (ref "R11") (pin "1") (pinfunction "1_1") (pintype "passive"))
      (node (ref "R39") (pin "1") (pinfunction "1_1") (pintype "passive"))
      (node (ref "R40") (pin "1") (pinfunction "1_1") (pintype "passive"))
      (node (ref "R41") (pin "1") (pinfunction "1_1") (pintype "passive"))
      (node (ref "R43") (pin "2") (pinfunction "2_2") (pintype "passive"))
      (node (ref "U2") (pin "3") (pinfunction "VDD_3") (pintype "passive"))
      (node (ref "U2") (pin "30") (pinfunction "VDD_30") (pintype "passive"))
      (node (ref "U2") (pin "48") (pinfunction "VDD_48") (pintype "passive"))
      (node (ref "U2") (pin "7") (pinfunction "VOUT33_7") (pintype "passive"))
    )
    (net (code "48") (name "5V") (class "Default")
      (node (ref "C1") (pin "1") (pinfunction "1_1") (pintype "passive"))
      (node (ref "C2") (pin "1") (pinfunction "1_1") (pintype "passive"))
      (node (ref "C6") (pin "1") (pinfunction "1_1") (pintype "passive"))
      (node (ref "C9") (pin "2") (pinfunction "2_2") (pintype "passive"))
      (node (ref "L1") (pin "1") (pinfunction "1_1") (pintype "passive"))
      (node (ref "U2") (pin "8") (pinfunction "VREGIN_8") (pintype "passive"))
      (node (ref "V1") (pin "3") (pinfunction "Vout_3") (pintype "passive"))
    )
    (net (code "49") (name "GND") (class "Default")
      (node (ref "C1") (pin "2") (pinfunction "2_2") (pintype "passive"))
      (node (ref "C10") (pin "1") (pinfunction "1_1") (pintype "passive"))
      (node (ref "C11") (pin "1") (pinfunction "1_1") (pintype "passive"))
      (node (ref "C12") (pin "1") (pinfunction "1_1") (pintype "passive"))
      (node (ref "C13") (pin "1") (pinfunction "1_1") (pintype "passive"))
      (node (ref "C14") (pin "1") (pinfunction "1_1") (pintype "passive"))
      (node (ref "C15") (pin "1") (pinfunction "1_1") (pintype "passive"))
      (node (ref "C16") (pin "1") (pinfunction "1_1") (pintype "passive"))
      (node (ref "C17") (pin "1") (pinfunction "1_1") (pintype "passive"))
      (node (ref "C18") (pin "1") (pinfunction "1_1") (pintype "passive"))
      (node (ref "C19") (pin "2") (pinfunction "2_2") (pintype "passive"))
      (node (ref "C2") (pin "2") (pinfunction "2_2") (pintype "passive"))
      (node (ref "C20") (pin "2") (pinfunction "2_2") (pintype "passive"))
      (node (ref "C21") (pin "1") (pinfunction "1_1") (pintype "passive"))
      (node (ref "C24") (pin "1") (pinfunction "1_1") (pintype "passive"))
      (node (ref "C25") (pin "1") (pinfunction "1_1") (pintype "passive"))
      (node (ref "C26") (pin "2") (pinfunction "2_2") (pintype "passive"))
      (node (ref "C27") (pin "1") (pinfunction "1_1") (pintype "passive"))
      (node (ref "C28") (pin "2") (pinfunction "2_2") (pintype "passive"))
      (node (ref "C29") (pin "2") (pinfunction "2_2") (pintype "passive"))
      (node (ref "C3") (pin "2") (pinfunction "2_2") (pintype "passive"))
      (node (ref "C30") (pin "2") (pinfunction "2_2") (pintype "passive"))
      (node (ref "C31") (pin "2") (pinfunction "2_2") (pintype "passive"))
      (node (ref "C5") (pin "2") (pinfunction "2_2") (pintype "passive"))
      (node (ref "C6") (pin "2") (pinfunction "2_2") (pintype "passive"))
      (node (ref "C7") (pin "1") (pinfunction "1_1") (pintype "passive"))
      (node (ref "C8") (pin "1") (pinfunction "1_1") (pintype "passive"))
      (node (ref "C9") (pin "1") (pinfunction "1_1") (pintype "passive"))
      (node (ref "D2") (pin "3") (pinfunction "0_3") (pintype "passive"))
      (node (ref "L3") (pin "2") (pinfunction "2_2") (pintype "passive"))
      (node (ref "P1") (pin "5") (pinfunction "5_5") (pintype "passive"))
      (node (ref "P2") (pin "3") (pinfunction "3_3") (pintype "passive"))
      (node (ref "P2") (pin "5") (pinfunction "5_5") (pintype "passive"))
      (node (ref "P7") (pin "1") (pinfunction "1_1") (pintype "passive"))
      (node (ref "P8") (pin "1") (pinfunction "GND_1") (pintype "passive"))
      (node (ref "Q13") (pin "3") (pinfunction "S_3") (pintype "passive"))
      (node (ref "Q14") (pin "3") (pinfunction "S_3") (pintype "passive"))
      (node (ref "Q15") (pin "3") (pinfunction "S_3") (pintype "passive"))
      (node (ref "Q16") (pin "2") (pinfunction "S_2") (pintype "passive"))
      (node (ref "Q17") (pin "2") (pinfunction "S_2") (pintype "passive"))
      (node (ref "Q18") (pin "2") (pinfunction "S_2") (pintype "passive"))
      (node (ref "Q3") (pin "2") (pinfunction "S_2") (pintype "passive"))
      (node (ref "Q4") (pin "2") (pinfunction "S_2") (pintype "passive"))
      (node (ref "Q5") (pin "1") (pinfunction "G_1") (pintype "passive"))
      (node (ref "Q6") (pin "2") (pinfunction "S_2") (pintype "passive"))
      (node (ref "Q7") (pin "2") (pinfunction "S_2") (pintype "passive"))
      (node (ref "Q8") (pin "2") (pinfunction "S_2") (pintype "passive"))
      (node (ref "Q9") (pin "2") (pinfunction "S_2") (pintype "passive"))
      (node (ref "R10") (pin "2") (pinfunction "2_2") (pintype "passive"))
      (node (ref "R13") (pin "2") (pinfunction "2_2") (pintype "passive"))
      (node (ref "R17") (pin "2") (pinfunction "2_2") (pintype "passive"))
      (node (ref "R18") (pin "1") (pinfunction "1_1") (pintype "passive"))
      (node (ref "R20") (pin "2") (pinfunction "2_2") (pintype "passive"))
      (node (ref "R24") (pin "2") (pinfunction "2_2") (pintype "passive"))
      (node (ref "R25") (pin "2") (pinfunction "2_2") (pintype "passive"))
      (node (ref "R26") (pin "2") (pinfunction "2_2") (pintype "passive"))
      (node (ref "R33") (pin "2") (pinfunction "2_2") (pintype "passive"))
      (node (ref "R34") (pin "2") (pinfunction "2_2") (pintype "passive"))
      (node (ref "R35") (pin "2") (pinfunction "2_2") (pintype "passive"))
      (node (ref "R44") (pin "2") (pinfunction "2_2") (pintype "passive"))
      (node (ref "R45") (pin "2") (pinfunction "2_2") (pintype "passive"))
      (node (ref "R7") (pin "1") (pinfunction "1_1") (pintype "passive"))
      (node (ref "R8") (pin "1") (pinfunction "1_1") (pintype "passive"))
      (node (ref "U1") (pin "4") (pinfunction "-_4") (pintype "passive"))
      (node (ref "U2") (pin "31") (pinfunction "VSS_31") (pintype "passive"))
      (node (ref "U2") (pin "4") (pinfunction "VSS_4") (pintype "passive"))
      (node (ref "U2") (pin "47") (pinfunction "VSS_47") (pintype "passive"))
      (node (ref "USB_1") (pin "5") (pinfunction "GND_5") (pintype "passive"))
      (node (ref "V1") (pin "1") (pinfunction "GND_1") (pintype "passive"))
    )
    (net (code "50") (name "Net-(C3-Pad1)") (class "Default")
      (node (ref "C3") (pin "1") (pinfunction "1_1") (pintype "passive"))
      (node (ref "R7") (pin "2") (pinfunction "2_2") (pintype "passive"))
      (node (ref "USB_1") (pin "6") (pinfunction "Shield_6") (pintype "passive"))
      (node (ref "USB_1") (pin "7") (pinfunction "Shield_7") (pintype "passive"))
      (node (ref "USB_1") (pin "8") (pinfunction "Shield_8") (pintype "passive"))
      (node (ref "USB_1") (pin "9") (pinfunction "Shield_9") (pintype "passive"))
    )
    (net (code "51") (name "Net-(C4-Pad1)") (class "Default")
      (node (ref "C4") (pin "1") (pinfunction "1_1") (pintype "passive"))
      (node (ref "D3") (pin "1") (pinfunction "0_1") (pintype "passive"))
      (node (ref "D3") (pin "2") (pinfunction "0_2") (pintype "passive"))
      (node (ref "D4") (pin "3") (pinfunction "0_3") (pintype "passive"))
    )
    (net (code "52") (name "Net-(C10-Pad2)") (class "Default")
      (node (ref "C10") (pin "2") (pinfunction "2_2") (pintype "passive"))
      (node (ref "R27") (pin "1") (pinfunction "1_1") (pintype "passive"))
      (node (ref "R28") (pin "2") (pinfunction "2_2") (pintype "passive"))
      (node (ref "R33") (pin "1") (pinfunction "1_1") (pintype "passive"))
    )
    (net (code "53") (name "Net-(C11-Pad2)") (class "Default")
      (node (ref "C11") (pin "2") (pinfunction "2_2") (pintype "passive"))
      (node (ref "R29") (pin "1") (pinfunction "1_1") (pintype "passive"))
      (node (ref "R30") (pin "2") (pinfunction "2_2") (pintype "passive"))
      (node (ref "R34") (pin "1") (pinfunction "1_1") (pintype "passive"))
    )
    (net (code "54") (name "Net-(C12-Pad2)") (class "Default")
      (node (ref "C12") (pin "2") (pinfunction "2_2") (pintype "passive"))
      (node (ref "R31") (pin "1") (pinfunction "1_1") (pintype "passive"))
      (node (ref "R32") (pin "2") (pinfunction "2_2") (pintype "passive"))
      (node (ref "R35") (pin "1") (pinfunction "1_1") (pintype "passive"))
    )
    (net (code "55") (name "Net-(D1-K)") (class "Default")
      (node (ref "D1") (pin "2") (pinfunction "K_2") (pintype "passive"))
      (node (ref "R10") (pin "1") (pinfunction "1_1") (pintype "passive"))
    )
    (net (code "56") (name "Net-(D5-K)") (class "Default")
      (node (ref "D5") (pin "2") (pinfunction "K_2") (pintype "passive"))
      (node (ref "R45") (pin "1") (pinfunction "1_1") (pintype "passive"))
    )
    (net (code "57") (name "Net-(D6-K)") (class "Default")
      (node (ref "D6") (pin "2") (pinfunction "K_2") (pintype "passive"))
      (node (ref "R44") (pin "1") (pinfunction "1_1") (pintype "passive"))
    )
    (net (code "58") (name "Net-(Q1-G)") (class "Default")
      (node (ref "Q1") (pin "1") (pinfunction "G_1") (pintype "passive"))
      (node (ref "R19") (pin "2") (pinfunction "2_2") (pintype "passive"))
      (node (ref "R3") (pin "2") (pinfunction "2_2") (pintype "passive"))
      (node (ref "U1") (pin "7") (pinfunction "2OUT_7") (pintype "passive"))
    )
    (net (code "59") (name "Net-(Q1-S)") (class "Default")
      (node (ref "Q1") (pin "3") (pinfunction "S_3") (pintype "passive"))
      (node (ref "R1") (pin "2") (pinfunction "2_2") (pintype "passive"))
      (node (ref "R3") (pin "1") (pinfunction "1_1") (pintype "passive"))
      (node (ref "R6") (pin "2") (pinfunction "2_2") (pintype "passive"))
    )
    (net (code "60") (name "Net-(Q2-D)") (class "Default")
      (node (ref "C4") (pin "2") (pinfunction "2_2") (pintype "passive"))
      (node (ref "Q2") (pin "3") (pinfunction "D_3") (pintype "passive"))
      (node (ref "R15") (pin "1") (pinfunction "1_1") (pintype "passive"))
    )
    (net (code "61") (name "Net-(Q2-G)") (class "Default")
      (node (ref "Q2") (pin "1") (pinfunction "G_1") (pintype "passive"))
      (node (ref "Q3") (pin "3") (pinfunction "D_3") (pintype "passive"))
      (node (ref "Q4") (pin "1") (pinfunction "G_1") (pintype "passive"))
      (node (ref "R9") (pin "2") (pinfunction "2_2") (pintype "passive"))
    )
    (net (code "62") (name "Net-(Q4-D)") (class "Default")
      (node (ref "Q4") (pin "3") (pinfunction "D_3") (pintype "passive"))
      (node (ref "R15") (pin "2") (pinfunction "2_2") (pintype "passive"))
    )
    (net (code "63") (name "Net-(Q6-D)") (class "Default")
      (node (ref "Q6") (pin "3") (pinfunction "D_3") (pintype "passive"))
      (node (ref "R14") (pin "2") (pinfunction "2_2") (pintype "passive"))
      (node (ref "R19") (pin "1") (pinfunction "1_1") (pintype "passive"))
      (node (ref "U1") (pin "5") (pinfunction "2+_5") (pintype "passive"))
    )
    (net (code "64") (name "Net-(Q10-G)") (class "Default")
      (node (ref "Q10") (pin "1") (pinfunction "G_1") (pintype "passive"))
      (node (ref "Q7") (pin "3") (pinfunction "D_3") (pintype "passive"))
      (node (ref "R21") (pin "2") (pinfunction "2_2") (pintype "passive"))
    )
    (net (code "65") (name "Net-(Q11-G)") (class "Default")
      (node (ref "Q11") (pin "1") (pinfunction "G_1") (pintype "passive"))
      (node (ref "Q8") (pin "3") (pinfunction "D_3") (pintype "passive"))
      (node (ref "R22") (pin "2") (pinfunction "2_2") (pintype "passive"))
    )
    (net (code "66") (name "Net-(Q12-G)") (class "Default")
      (node (ref "Q12") (pin "1") (pinfunction "G_1") (pintype "passive"))
      (node (ref "Q9") (pin "3") (pinfunction "D_3") (pintype "passive"))
      (node (ref "R23") (pin "2") (pinfunction "2_2") (pintype "passive"))
    )
    (net (code "67") (name "Net-(Q13-G)") (class "Default")
      (node (ref "Q13") (pin "1") (pinfunction "G_1") (pintype "passive"))
      (node (ref "Q16") (pin "3") (pinfunction "D_3") (pintype "passive"))
      (node (ref "R36") (pin "2") (pinfunction "2_2") (pintype "passive"))
    )
    (net (code "68") (name "Net-(Q14-G)") (class "Default")
      (node (ref "Q14") (pin "1") (pinfunction "G_1") (pintype "passive"))
      (node (ref "Q17") (pin "3") (pinfunction "D_3") (pintype "passive"))
      (node (ref "R37") (pin "2") (pinfunction "2_2") (pintype "passive"))
    )
    (net (code "69") (name "Net-(Q15-G)") (class "Default")
      (node (ref "Q15") (pin "1") (pinfunction "G_1") (pintype "passive"))
      (node (ref "Q18") (pin "3") (pinfunction "D_3") (pintype "passive"))
      (node (ref "R38") (pin "2") (pinfunction "2_2") (pintype "passive"))
    )
    (net (code "70") (name "Net-(U1A-1+)") (class "Default")
      (node (ref "R5") (pin "2") (pinfunction "2_2") (pintype "passive"))
      (node (ref "R8") (pin "2") (pinfunction "2_2") (pintype "passive"))
      (node (ref "U1") (pin "3") (pinfunction "1+_3") (pintype "passive"))
    )
    (net (code "71") (name "Net-(U1A-1-)") (class "Default")
      (node (ref "R12") (pin "2") (pinfunction "2_2") (pintype "passive"))
      (node (ref "R6") (pin "1") (pinfunction "1_1") (pintype "passive"))
      (node (ref "U1") (pin "2") (pinfunction "1-_2") (pintype "passive"))
    )
    (net (code "72") (name "Net-(U1A-1OUT)") (class "Default")
      (node (ref "R12") (pin "1") (pinfunction "1_1") (pintype "passive"))
      (node (ref "R14") (pin "1") (pinfunction "1_1") (pintype "passive"))
      (node (ref "R16") (pin "2") (pinfunction "2_2") (pintype "passive"))
      (node (ref "U1") (pin "1") (pinfunction "1OUT_1") (pintype "passive"))
    )
    (net (code "73") (name "Net-(U1B-2-)") (class "Default")
      (node (ref "R11") (pin "2") (pinfunction "2_2") (pintype "passive"))
      (node (ref "R17") (pin "1") (pinfunction "1_1") (pintype "passive"))
      (node (ref "U1") (pin "6") (pinfunction "2-_6") (pintype "passive"))
    )
    (net (code "74") (name "Net-(U2A-VDDA)") (class "Default")
      (node (ref "C22") (pin "2") (pinfunction "2_2") (pintype "passive"))
      (node (ref "C23") (pin "2") (pinfunction "2_2") (pintype "passive"))
      (node (ref "L2") (pin "1") (pinfunction "1_1") (pintype "passive"))
      (node (ref "U2") (pin "13") (pinfunction "VDDA_13") (pintype "passive"))
      (node (ref "U2") (pin "14") (pinfunction "VREFH_14") (pintype "passive"))
    )
    (net (code "75") (name "Net-(U2A-VREFL)") (class "Default")
      (node (ref "C22") (pin "1") (pinfunction "1_1") (pintype "passive"))
      (node (ref "C23") (pin "1") (pinfunction "1_1") (pintype "passive"))
      (node (ref "L3") (pin "1") (pinfunction "1_1") (pintype "passive"))
      (node (ref "U2") (pin "15") (pinfunction "VREFL_15") (pintype "passive"))
      (node (ref "U2") (pin "16") (pinfunction "VSSA_16") (pintype "passive"))
    )
    (net (code "76") (name "Net-(USB_1-VBUS)") (class "Default")
      (node (ref "L1") (pin "2") (pinfunction "2_2") (pintype "passive"))
      (node (ref "USB_1") (pin "1") (pinfunction "VBUS_1") (pintype "passive"))
    )
    (net (code "77") (name "VBAT") (class "Default")
      (node (ref "C28") (pin "1") (pinfunction "1_1") (pintype "passive"))
      (node (ref "C8") (pin "2") (pinfunction "2_2") (pintype "passive"))
      (node (ref "D3") (pin "3") (pinfunction "0_3") (pintype "passive"))
      (node (ref "D5") (pin "1") (pinfunction "A_1") (pintype "passive"))
      (node (ref "P1") (pin "2") (pinfunction "2_2") (pintype "passive"))
      (node (ref "Q2") (pin "2") (pinfunction "S_2") (pintype "passive"))
      (node (ref "Q5") (pin "3") (pinfunction "S_3") (pintype "passive"))
      (node (ref "R1") (pin "1") (pinfunction "1_1") (pintype "passive"))
      (node (ref "R5") (pin "1") (pinfunction "1_1") (pintype "passive"))
      (node (ref "R9") (pin "1") (pinfunction "1_1") (pintype "passive"))
      (node (ref "V1") (pin "2") (pinfunction "Vin_2") (pintype "passive"))
    )
    (net (code "78") (name "VP1") (class "Default")
      (node (ref "C29") (pin "1") (pinfunction "1_1") (pintype "passive"))
      (node (ref "C30") (pin "1") (pinfunction "1_1") (pintype "passive"))
      (node (ref "C31") (pin "1") (pinfunction "1_1") (pintype "passive"))
      (node (ref "D1") (pin "1") (pinfunction "A_1") (pintype "passive"))
      (node (ref "P1") (pin "1") (pinfunction "1_1") (pintype "passive"))
      (node (ref "Q1") (pin "4") (pinfunction "D_4") (pintype "passive"))
      (node (ref "Q10") (pin "3") (pinfunction "S_3") (pintype "passive"))
      (node (ref "Q11") (pin "3") (pinfunction "S_3") (pintype "passive"))
      (node (ref "Q12") (pin "3") (pinfunction "S_3") (pintype "passive"))
      (node (ref "R21") (pin "1") (pinfunction "1_1") (pintype "passive"))
      (node (ref "R22") (pin "1") (pinfunction "1_1") (pintype "passive"))
      (node (ref "R23") (pin "1") (pinfunction "1_1") (pintype "passive"))
      (node (ref "R36") (pin "1") (pinfunction "1_1") (pintype "passive"))
      (node (ref "R37") (pin "1") (pinfunction "1_1") (pintype "passive"))
      (node (ref "R38") (pin "1") (pinfunction "1_1") (pintype "passive"))
    )
    (net (code "79") (name "VPump") (class "Default")
      (node (ref "C27") (pin "2") (pinfunction "2_2") (pintype "passive"))
      (node (ref "C5") (pin "1") (pinfunction "1_1") (pintype "passive"))
      (node (ref "D4") (pin "1") (pinfunction "0_1") (pintype "passive"))
      (node (ref "D4") (pin "2") (pinfunction "0_2") (pintype "passive"))
      (node (ref "P1") (pin "3") (pinfunction "3_3") (pintype "passive"))
      (node (ref "U1") (pin "8") (pinfunction "+_8") (pintype "passive"))
    )
    (net (code "80") (name "Vin") (class "Default")
      (node (ref "C7") (pin "2") (pinfunction "2_2") (pintype "passive"))
      (node (ref "P3") (pin "1") (pinfunction "1_1") (pintype "passive"))
      (node (ref "Q5") (pin "4") (pinfunction "D_4") (pintype "passive"))
    )
    (net (code "81") (name "unconnected-(P2-Pad6)") (class "Default")
      (node (ref "P2") (pin "6") (pinfunction "6_6") (pintype "passive"))
    )
    (net (code "82") (name "unconnected-(P2-Pad7)") (class "Default")
      (node (ref "P2") (pin "7") (pinfunction "7_7") (pintype "passive"))
    )
    (net (code "83") (name "unconnected-(P2-Pad8)") (class "Default")
      (node (ref "P2") (pin "8") (pinfunction "8_8") (pintype "passive"))
    )
    (net (code "84") (name "unconnected-(P2-Pad9)") (class "Default")
      (node (ref "P2") (pin "9") (pinfunction "9_9") (pintype "passive"))
    )
    (net (code "85") (name "unconnected-(P12-Pad10)") (class "Default")
      (node (ref "P12") (pin "10") (pinfunction "10_10") (pintype "passive"))
    )
    (net (code "86") (name "unconnected-(U2A-PTE0-Pad1)") (class "Default")
      (node (ref "U2") (pin "1") (pinfunction "PTE0_1") (pintype "passive"))
    )
    (net (code "87") (name "unconnected-(U2A-PTE1-Pad2)") (class "Default")
      (node (ref "U2") (pin "2") (pinfunction "PTE1_2") (pintype "passive"))
    )
    (net (code "88") (name "unconnected-(U2A-PTE20-Pad9)") (class "Default")
      (node (ref "U2") (pin "9") (pinfunction "PTE20_9") (pintype "passive"))
    )
    (net (code "89") (name "unconnected-(U2A-PTE21-Pad10)") (class "Default")
      (node (ref "U2") (pin "10") (pinfunction "PTE21_10") (pintype "passive"))
    )
    (net (code "90") (name "unconnected-(U2A-PTE22-Pad11)") (class "Default")
      (node (ref "U2") (pin "11") (pinfunction "PTE22_11") (pintype "passive"))
    )
    (net (code "91") (name "unconnected-(U2A-PTE23-Pad12)") (class "Default")
      (node (ref "U2") (pin "12") (pinfunction "PTE23_12") (pintype "passive"))
    )
    (net (code "92") (name "unconnected-(U2B-PTA1-Pad23)") (class "Default")
      (node (ref "U2") (pin "23") (pinfunction "PTA1_23") (pintype "passive"))
    )
    (net (code "93") (name "unconnected-(U2B-PTA2-Pad24)") (class "Default")
      (node (ref "U2") (pin "24") (pinfunction "PTA2_24") (pintype "passive"))
    )
    (net (code "94") (name "unconnected-(U2B-PTA4-Pad26)") (class "Default")
      (node (ref "U2") (pin "26") (pinfunction "PTA4_26") (pintype "passive"))
    )
    (net (code "95") (name "unconnected-(U2B-PTA5-Pad27)") (class "Default")
      (node (ref "U2") (pin "27") (pinfunction "PTA5_27") (pintype "passive"))
    )
    (net (code "96") (name "unconnected-(U2B-PTA12-Pad28)") (class "Default")
      (node (ref "U2") (pin "28") (pinfunction "PTA12_28") (pintype "passive"))
    )
    (net (code "97") (name "unconnected-(U2B-PTA13-Pad29)") (class "Default")
      (node (ref "U2") (pin "29") (pinfunction "PTA13_29") (pintype "passive"))
    )
    (net (code "98") (name "unconnected-(U2B-PTE24-Pad20)") (class "Default")
      (node (ref "U2") (pin "20") (pinfunction "PTE24_20") (pintype "passive"))
    )
    (net (code "99") (name "unconnected-(U2B-PTE25-Pad21)") (class "Default")
      (node (ref "U2") (pin "21") (pinfunction "PTE25_21") (pintype "passive"))
    )
    (net (code "100") (name "unconnected-(U2B-PTE29-Pad17)") (class "Default")
      (node (ref "U2") (pin "17") (pinfunction "PTE29_17") (pintype "passive"))
    )
    (net (code "101") (name "unconnected-(U2B-PTE30-Pad18)") (class "Default")
      (node (ref "U2") (pin "18") (pinfunction "PTE30_18") (pintype "passive"))
    )
    (net (code "102") (name "unconnected-(U2B-PTE31-Pad19)") (class "Default")
      (node (ref "U2") (pin "19") (pinfunction "PTE31_19") (pintype "passive"))
    )
    (net (code "103") (name "unconnected-(U2D-PTC5{slash}LLWU_P9-Pad50)") (class "Default")
      (node (ref "U2") (pin "50") (pinfunction "PTC5/LLWU_P9_50") (pintype "passive"))
    )
    (net (code "104") (name "unconnected-(U2D-PTC6{slash}LLWU_P10-Pad51)") (class "Default")
      (node (ref "U2") (pin "51") (pinfunction "PTC6/LLWU_P10_51") (pintype "passive"))
    )
    (net (code "105") (name "unconnected-(U2D-PTC7-Pad52)") (class "Default")
      (node (ref "U2") (pin "52") (pinfunction "PTC7_52") (pintype "passive"))
    )
    (net (code "106") (name "unconnected-(U2D-PTC10-Pad55)") (class "Default")
      (node (ref "U2") (pin "55") (pinfunction "PTC10_55") (pintype "passive"))
    )
    (net (code "107") (name "unconnected-(U2D-PTC11-Pad56)") (class "Default")
      (node (ref "U2") (pin "56") (pinfunction "PTC11_56") (pintype "passive"))
    )
    (net (code "108") (name "unconnected-(U2D-PTD4{slash}LLWU_P14-Pad61)") (class "Default")
      (node (ref "U2") (pin "61") (pinfunction "PTD4/LLWU_P14_61") (pintype "passive"))
    )
    (net (code "109") (name "unconnected-(U2D-PTD5-Pad62)") (class "Default")
      (node (ref "U2") (pin "62") (pinfunction "PTD5_62") (pintype "passive"))
    )
    (net (code "110") (name "unconnected-(USB_1-NC-Pad4)") (class "Default")
      (node (ref "USB_1") (pin "4") (pinfunction "NC_4") (pintype "passive"))
    )
  )
)
